# dodocohedreled.net
KiCad netlist of a schematic drawn in EAGLE
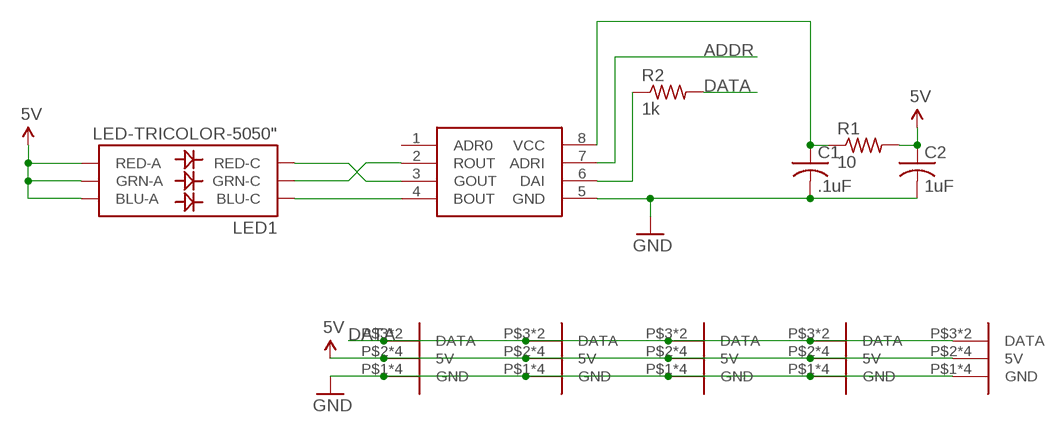
[diagram p0: schematic, sheet 1]

(export (version "E")
  (design (tool "Eeschema 10.0.6"))
  (components
    (comp (ref "C1")
      (value ".1uF")
      (footprint "eagle-import:C0603")
      (libsource (lib "eagle-import") (part "C-USC0603"))
    )
    (comp (ref "C2")
      (value "1uF")
      (footprint "eagle-import:C0603")
      (libsource (lib "eagle-import") (part "C-USC0603"))
    )
    (comp (ref "LED1")
      (value "LED-TRICOLOR-5050\"")
      (footprint "eagle-import:LED-TRICOLOR-5050-FIXED")
      (libsource (lib "eagle-import") (part "LED-TRICOLOR-5050{dblquote}"))
    )
    (comp (ref "R1")
      (value "10")
      (footprint "eagle-import:R0603")
      (libsource (lib "eagle-import") (part "R-US_R0603"))
    )
    (comp (ref "R2")
      (value "1k")
      (footprint "eagle-import:R0603")
      (libsource (lib "eagle-import") (part "R-US_R0603"))
    )
    (comp (ref "U$1")
      (value "WS2821A")
      (footprint "eagle-import:SOP8")
      (libsource (lib "eagle-import") (part "WS2821A"))
    )
    (comp (ref "U$2")
      (value "D_EDGESLOT")
      (footprint "eagle-import:D_EDGE_SLOT")
      (libsource (lib "eagle-import") (part "D_EDGESLOT"))
    )
    (comp (ref "U$3")
      (value "D_EDGESLOT")
      (footprint "eagle-import:D_EDGE_SLOT")
      (libsource (lib "eagle-import") (part "D_EDGESLOT"))
    )
    (comp (ref "U$4")
      (value "D_EDGESLOT")
      (footprint "eagle-import:D_EDGE_SLOT")
      (libsource (lib "eagle-import") (part "D_EDGESLOT"))
    )
    (comp (ref "U$5")
      (value "D_EDGESLOT")
      (footprint "eagle-import:D_EDGE_SLOT")
      (libsource (lib "eagle-import") (part "D_EDGESLOT"))
    )
    (comp (ref "U$6")
      (value "D_EDGESLOT")
      (footprint "eagle-import:D_EDGE_SLOT")
      (libsource (lib "eagle-import") (part "D_EDGESLOT"))
    )
  )
  (nets
    (net (code "1") (name "/ADDR") (class "Default")
      (node (ref "U$1") (pin "7") (pinfunction "ADRI_7") (pintype "bidirectional"))
    )
    (net (code "2") (name "/DATA") (class "Default")
      (node (ref "R2") (pin "2") (pinfunction "2_2") (pintype "passive"))
      (node (ref "U$2") (pin "P$3") (pinfunction "DATA_P$3") (pintype "bidirectional"))
      (node (ref "U$2") (pin "P$8") (pinfunction "DATA_P$8") (pintype "bidirectional"))
      (node (ref "U$3") (pin "P$3") (pinfunction "DATA_P$3") (pintype "bidirectional"))
      (node (ref "U$3") (pin "P$8") (pinfunction "DATA_P$8") (pintype "bidirectional"))
      (node (ref "U$4") (pin "P$3") (pinfunction "DATA_P$3") (pintype "bidirectional"))
      (node (ref "U$4") (pin "P$8") (pinfunction "DATA_P$8") (pintype "bidirectional"))
      (node (ref "U$5") (pin "P$3") (pinfunction "DATA_P$3") (pintype "bidirectional"))
      (node (ref "U$5") (pin "P$8") (pinfunction "DATA_P$8") (pintype "bidirectional"))
      (node (ref "U$6") (pin "P$3") (pinfunction "DATA_P$3") (pintype "bidirectional"))
      (node (ref "U$6") (pin "P$8") (pinfunction "DATA_P$8") (pintype "bidirectional"))
    )
    (net (code "3") (name "5V") (class "Default")
      (node (ref "C2") (pin "1") (pinfunction "1_1") (pintype "passive"))
      (node (ref "LED1") (pin "4") (pinfunction "GRN-A_4") (pintype "bidirectional"))
      (node (ref "LED1") (pin "5") (pinfunction "RED-A_5") (pintype "bidirectional"))
      (node (ref "LED1") (pin "6") (pinfunction "BLU-A_6") (pintype "bidirectional"))
      (node (ref "R1") (pin "2") (pinfunction "2_2") (pintype "passive"))
      (node (ref "U$2") (pin "P$2") (pinfunction "5V_P$2") (pintype "bidirectional"))
      (node (ref "U$2") (pin "P$4") (pinfunction "5V_P$4") (pintype "bidirectional"))
      (node (ref "U$2") (pin "P$7") (pinfunction "5V_P$7") (pintype "bidirectional"))
      (node (ref "U$2") (pin "P$9") (pinfunction "5V_P$9") (pintype "bidirectional"))
      (node (ref "U$3") (pin "P$2") (pinfunction "5V_P$2") (pintype "bidirectional"))
      (node (ref "U$3") (pin "P$4") (pinfunction "5V_P$4") (pintype "bidirectional"))
      (node (ref "U$3") (pin "P$7") (pinfunction "5V_P$7") (pintype "bidirectional"))
      (node (ref "U$3") (pin "P$9") (pinfunction "5V_P$9") (pintype "bidirectional"))
      (node (ref "U$4") (pin "P$2") (pinfunction "5V_P$2") (pintype "bidirectional"))
      (node (ref "U$4") (pin "P$4") (pinfunction "5V_P$4") (pintype "bidirectional"))
      (node (ref "U$4") (pin "P$7") (pinfunction "5V_P$7") (pintype "bidirectional"))
      (node (ref "U$4") (pin "P$9") (pinfunction "5V_P$9") (pintype "bidirectional"))
      (node (ref "U$5") (pin "P$2") (pinfunction "5V_P$2") (pintype "bidirectional"))
      (node (ref "U$5") (pin "P$4") (pinfunction "5V_P$4") (pintype "bidirectional"))
      (node (ref "U$5") (pin "P$7") (pinfunction "5V_P$7") (pintype "bidirectional"))
      (node (ref "U$5") (pin "P$9") (pinfunction "5V_P$9") (pintype "bidirectional"))
      (node (ref "U$6") (pin "P$2") (pinfunction "5V_P$2") (pintype "bidirectional"))
      (node (ref "U$6") (pin "P$4") (pinfunction "5V_P$4") (pintype "bidirectional"))
      (node (ref "U$6") (pin "P$7") (pinfunction "5V_P$7") (pintype "bidirectional"))
      (node (ref "U$6") (pin "P$9") (pinfunction "5V_P$9") (pintype "bidirectional"))
    )
    (net (code "4") (name "GND") (class "Default")
      (node (ref "C1") (pin "2") (pinfunction "2_2") (pintype "passive"))
      (node (ref "C2") (pin "2") (pinfunction "2_2") (pintype "passive"))
      (node (ref "U$1") (pin "5") (pinfunction "GND_5") (pintype "bidirectional"))
      (node (ref "U$2") (pin "P$1") (pinfunction "GND_P$1") (pintype "bidirectional"))
      (node (ref "U$2") (pin "P$10") (pinfunction "GND_P$10") (pintype "bidirectional"))
      (node (ref "U$2") (pin "P$5") (pinfunction "GND_P$5") (pintype "bidirectional"))
      (node (ref "U$2") (pin "P$6") (pinfunction "GND_P$6") (pintype "bidirectional"))
      (node (ref "U$3") (pin "P$1") (pinfunction "GND_P$1") (pintype "bidirectional"))
      (node (ref "U$3") (pin "P$10") (pinfunction "GND_P$10") (pintype "bidirectional"))
      (node (ref "U$3") (pin "P$5") (pinfunction "GND_P$5") (pintype "bidirectional"))
      (node (ref "U$3") (pin "P$6") (pinfunction "GND_P$6") (pintype "bidirectional"))
      (node (ref "U$4") (pin "P$1") (pinfunction "GND_P$1") (pintype "bidirectional"))
      (node (ref "U$4") (pin "P$10") (pinfunction "GND_P$10") (pintype "bidirectional"))
      (node (ref "U$4") (pin "P$5") (pinfunction "GND_P$5") (pintype "bidirectional"))
      (node (ref "U$4") (pin "P$6") (pinfunction "GND_P$6") (pintype "bidirectional"))
      (node (ref "U$5") (pin "P$1") (pinfunction "GND_P$1") (pintype "bidirectional"))
      (node (ref "U$5") (pin "P$10") (pinfunction "GND_P$10") (pintype "bidirectional"))
      (node (ref "U$5") (pin "P$5") (pinfunction "GND_P$5") (pintype "bidirectional"))
      (node (ref "U$5") (pin "P$6") (pinfunction "GND_P$6") (pintype "bidirectional"))
      (node (ref "U$6") (pin "P$1") (pinfunction "GND_P$1") (pintype "bidirectional"))
      (node (ref "U$6") (pin "P$10") (pinfunction "GND_P$10") (pintype "bidirectional"))
      (node (ref "U$6") (pin "P$5") (pinfunction "GND_P$5") (pintype "bidirectional"))
      (node (ref "U$6") (pin "P$6") (pinfunction "GND_P$6") (pintype "bidirectional"))
    )
    (net (code "5") (name "Net-(LED1-BLU-C)") (class "Default")
      (node (ref "LED1") (pin "1") (pinfunction "BLU-C_1") (pintype "bidirectional"))
      (node (ref "U$1") (pin "4") (pinfunction "BOUT_4") (pintype "bidirectional"))
    )
    (net (code "6") (name "Net-(LED1-GRN-C)") (class "Default")
      (node (ref "LED1") (pin "3") (pinfunction "GRN-C_3") (pintype "bidirectional"))
      (node (ref "U$1") (pin "2") (pinfunction "ROUT_2") (pintype "bidirectional"))
    )
    (net (code "7") (name "Net-(LED1-RED-C)") (class "Default")
      (node (ref "LED1") (pin "2") (pinfunction "RED-C_2") (pintype "bidirectional"))
      (node (ref "U$1") (pin "3") (pinfunction "GOUT_3") (pintype "bidirectional"))
    )
    (net (code "8") (name "Net-(U$1-DAI)") (class "Default")
      (node (ref "R2") (pin "1") (pinfunction "1_1") (pintype "passive"))
      (node (ref "U$1") (pin "6") (pinfunction "DAI_6") (pintype "bidirectional"))
    )
    (net (code "9") (name "Net-(U$1-VCC)") (class "Default")
      (node (ref "C1") (pin "1") (pinfunction "1_1") (pintype "passive"))
      (node (ref "R1") (pin "1") (pinfunction "1_1") (pintype "passive"))
      (node (ref "U$1") (pin "8") (pinfunction "VCC_8") (pintype "bidirectional"))
    )
    (net (code "10") (name "unconnected-(U$1-ADR0-Pad1)") (class "Default")
      (node (ref "U$1") (pin "1") (pinfunction "ADR0_1") (pintype "bidirectional"))
    )
  )
)
